# tomo.net
KiCad netlist of a schematic drawn in EAGLE
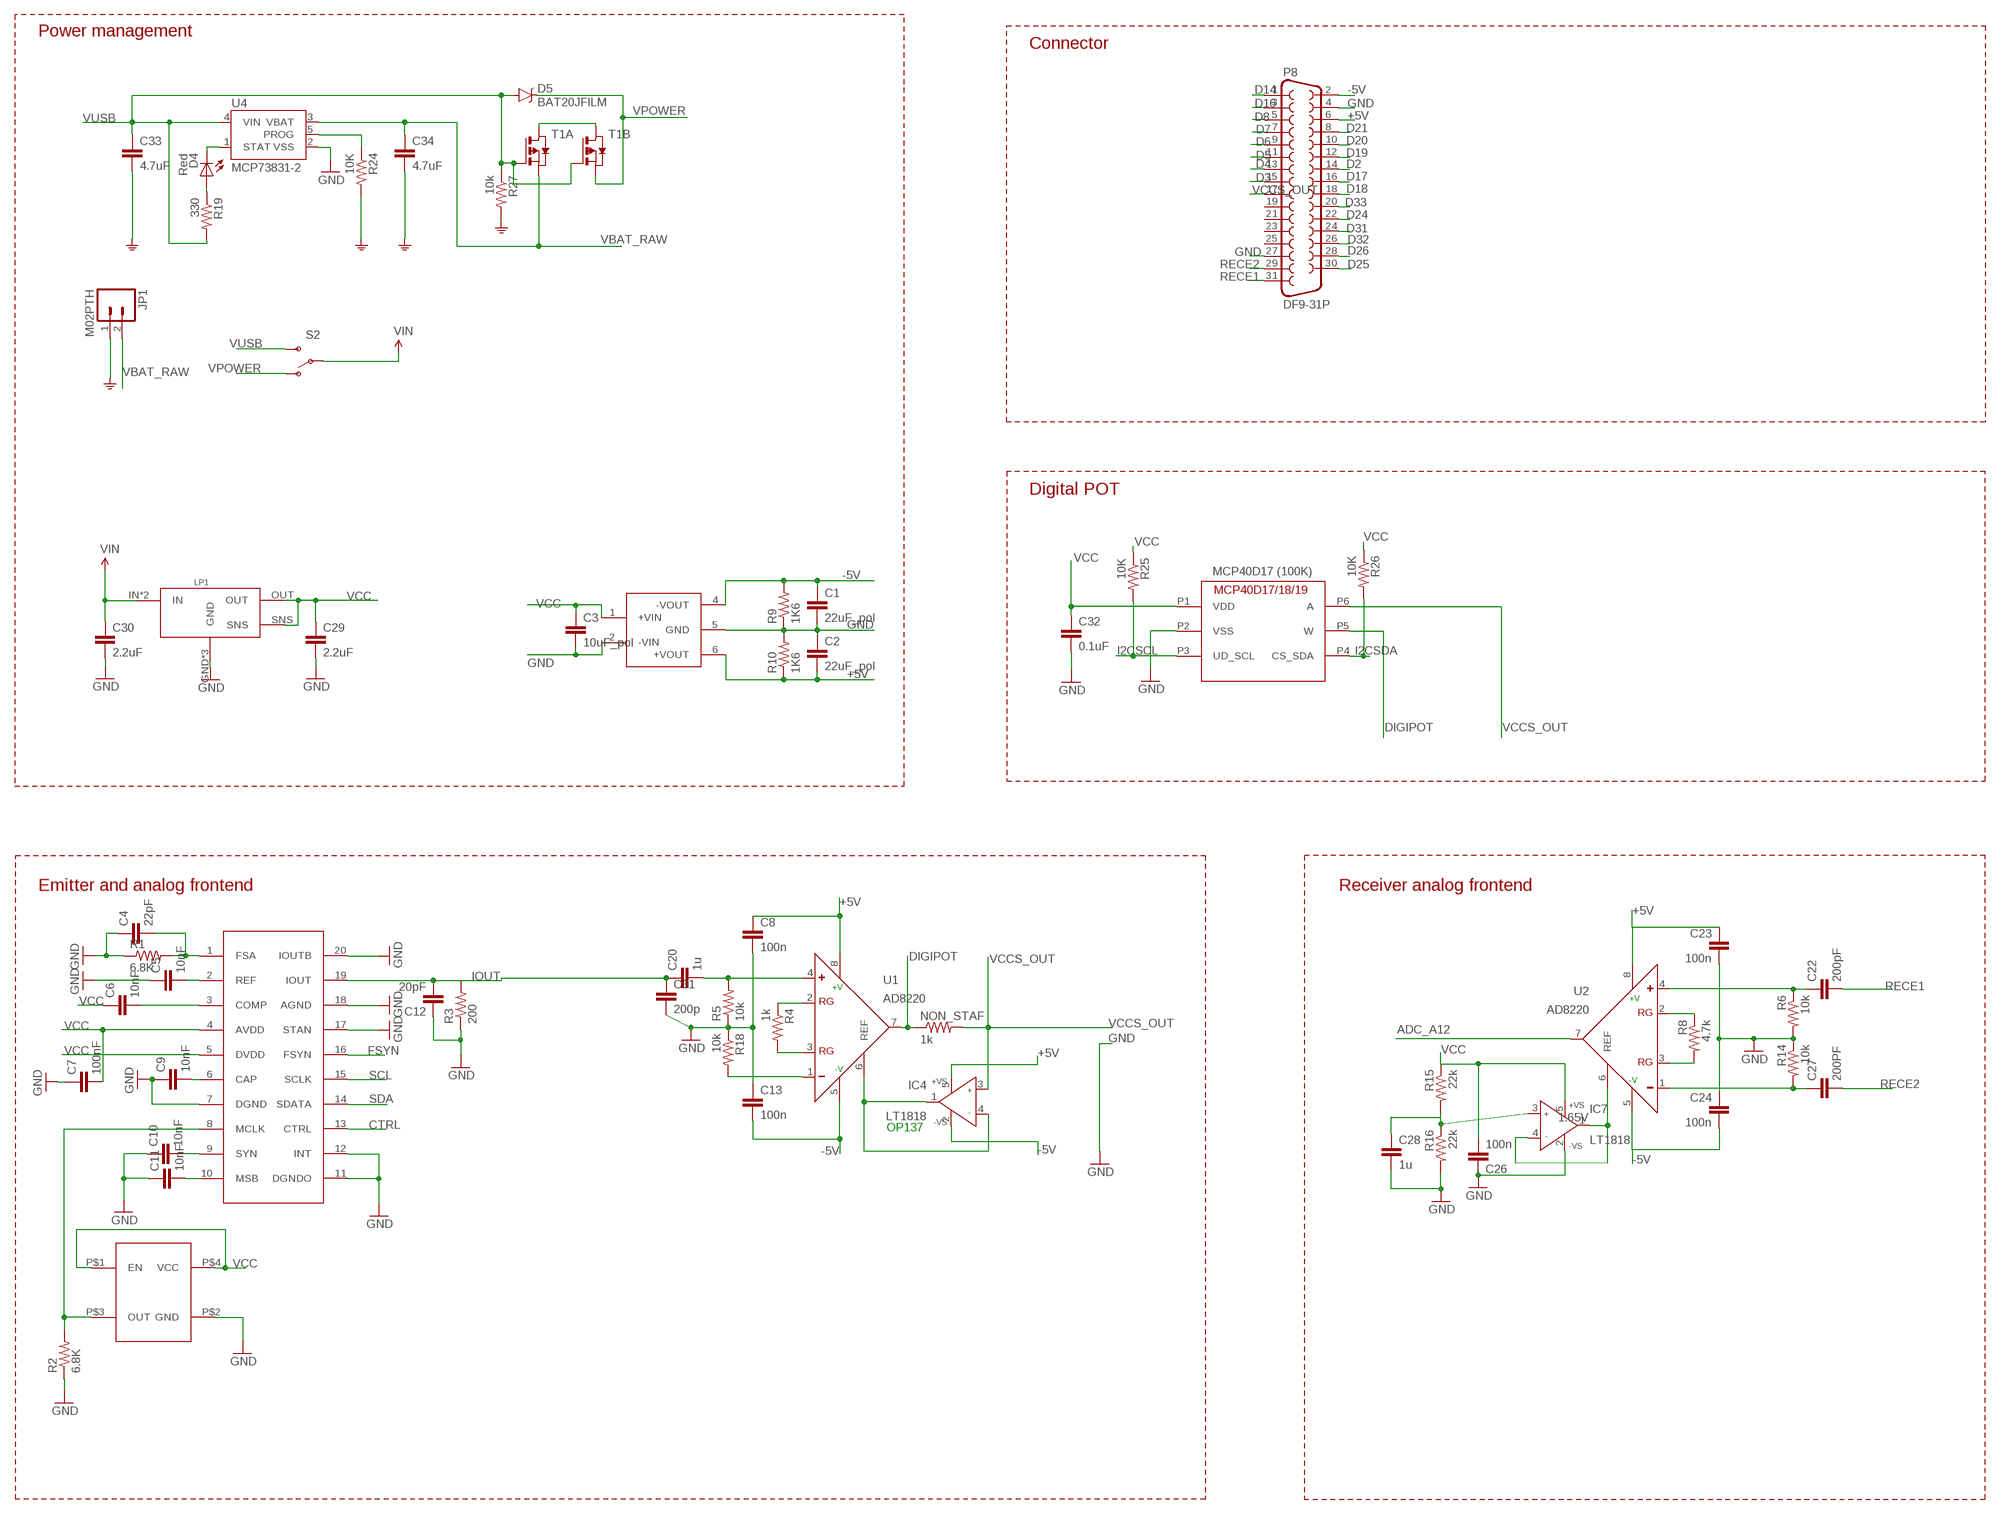
[diagram p0: schematic, sheet 1]
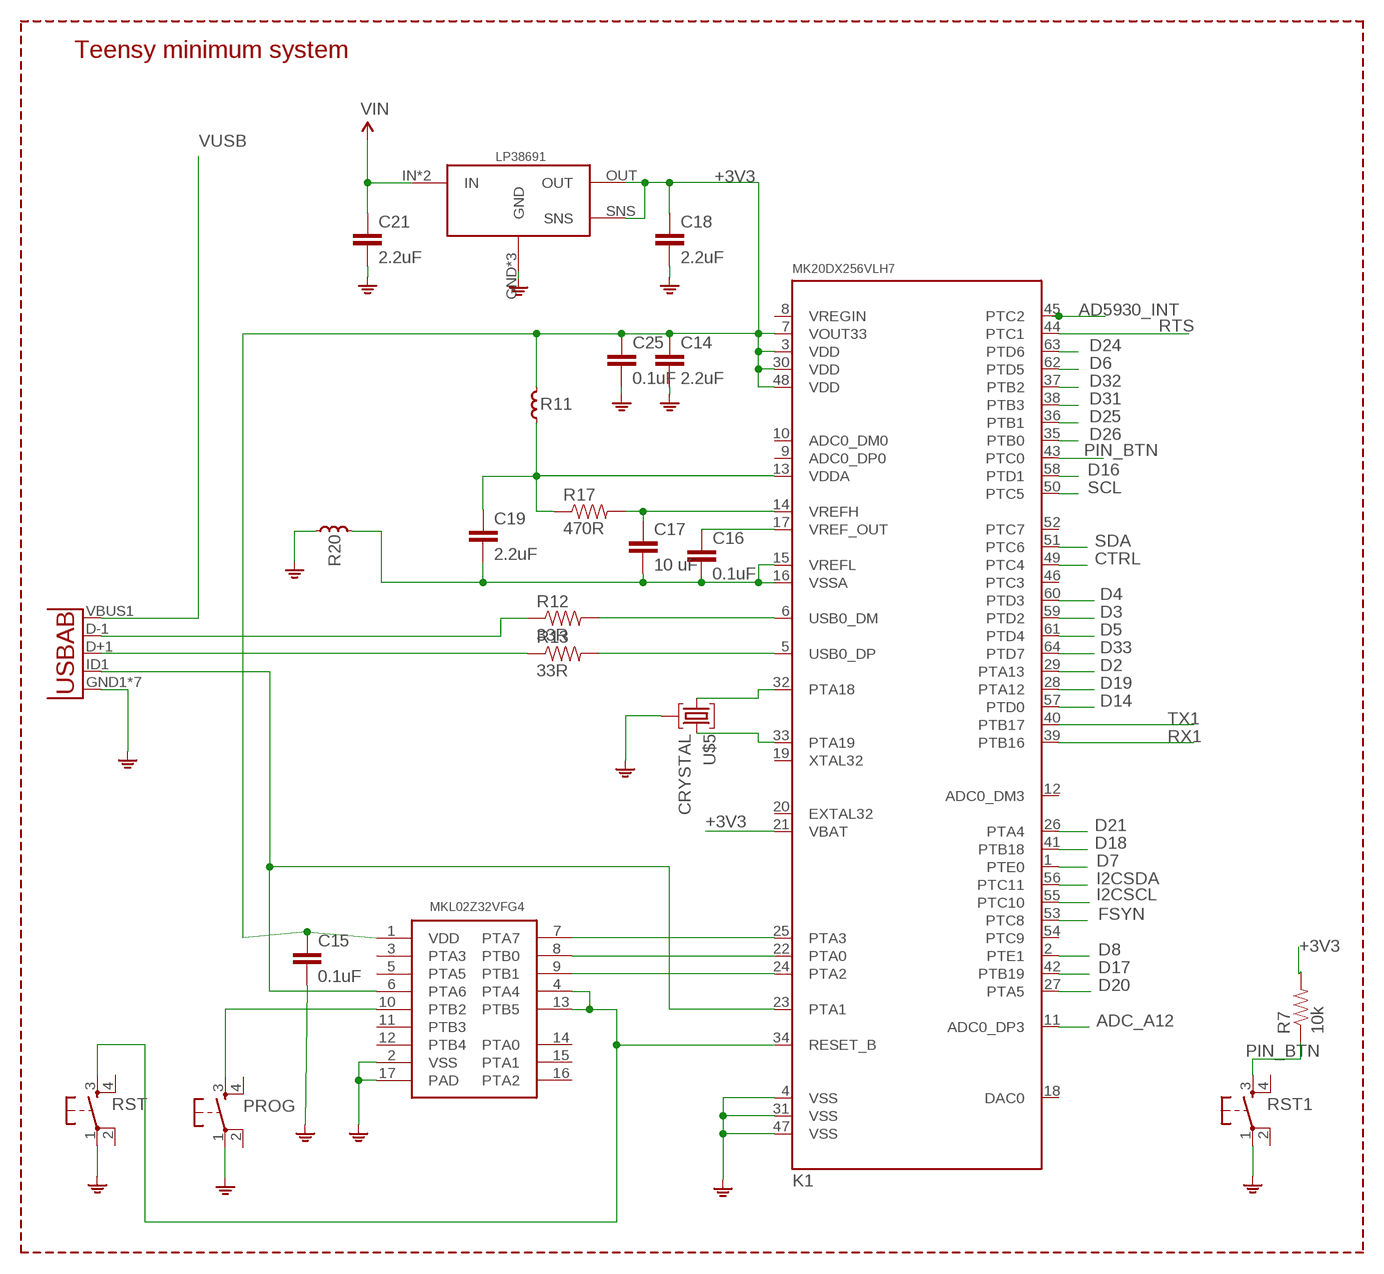
[diagram p1: schematic, sheet 2]
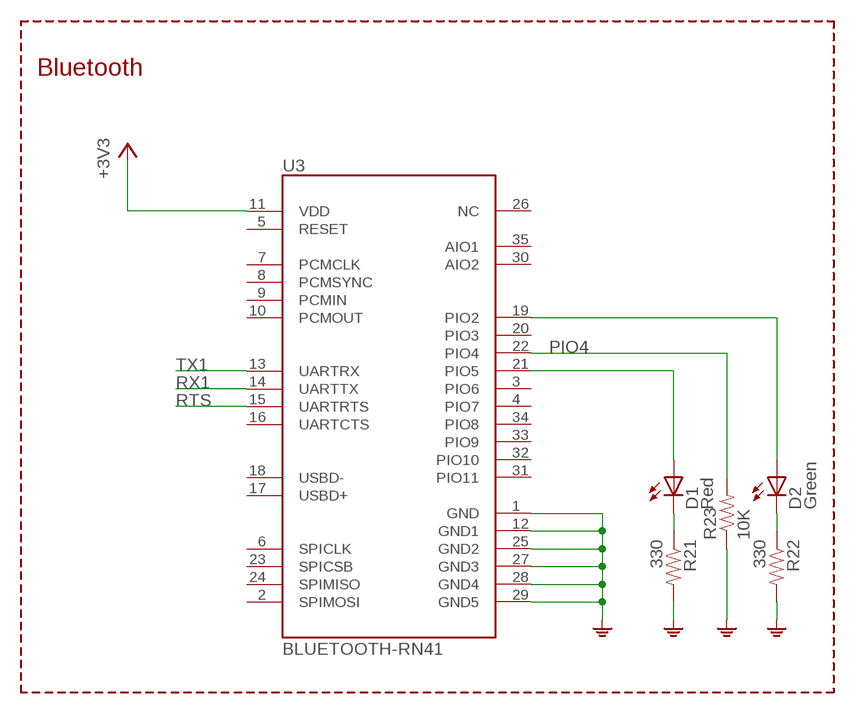
[diagram p2: schematic, sheet 3]

(export (version "E")
  (design (tool "Eeschema 10.0.6"))
  (components
    (comp (ref "C1")
      (value "22uF_pol")
      (footprint "eagle-import:0603-CAP")
      (libsource (lib "eagle-import") (part "0.1UF-25V(+80/-20%)(0603)"))
    )
    (comp (ref "C2")
      (value "22uF_pol")
      (footprint "eagle-import:0603-CAP")
      (libsource (lib "eagle-import") (part "0.1UF-25V(+80/-20%)(0603)"))
    )
    (comp (ref "C3")
      (value "10uF_pol")
      (footprint "eagle-import:0603-CAP")
      (libsource (lib "eagle-import") (part "0.1UF-25V(+80/-20%)(0603)"))
    )
    (comp (ref "C4")
      (value "22pF")
      (footprint "eagle-import:0603-CAP")
      (libsource (lib "eagle-import") (part "1.0UF-16V-10%(0603)"))
    )
    (comp (ref "C5")
      (value "10nF")
      (footprint "eagle-import:0603-CAP")
      (libsource (lib "eagle-import") (part "1.0UF-16V-10%(0603)"))
    )
    (comp (ref "C6")
      (value "10nF")
      (footprint "eagle-import:0603-CAP")
      (libsource (lib "eagle-import") (part "1.0UF-16V-10%(0603)"))
    )
    (comp (ref "C7")
      (value "100nF")
      (footprint "eagle-import:0603-CAP")
      (libsource (lib "eagle-import") (part "1.0UF-16V-10%(0603)"))
    )
    (comp (ref "C8")
      (value "100n")
      (footprint "eagle-import:0603-CAP")
      (libsource (lib "eagle-import") (part "0.1UF-25V(+80/-20%)(0603)"))
    )
    (comp (ref "C9")
      (value "10nF")
      (footprint "eagle-import:0603-CAP")
      (libsource (lib "eagle-import") (part "1.0UF-16V-10%(0603)"))
    )
    (comp (ref "C10")
      (value "10nF")
      (footprint "eagle-import:0603-CAP")
      (libsource (lib "eagle-import") (part "1.0UF-16V-10%(0603)"))
    )
    (comp (ref "C11")
      (value "10nF")
      (footprint "eagle-import:0603-CAP")
      (libsource (lib "eagle-import") (part "1.0UF-16V-10%(0603)"))
    )
    (comp (ref "C12")
      (value "20pF")
      (footprint "eagle-import:0603-CAP")
      (libsource (lib "eagle-import") (part "1.0UF-16V-10%(0603)"))
    )
    (comp (ref "C13")
      (value "100n")
      (footprint "eagle-import:0603-CAP")
      (libsource (lib "eagle-import") (part "0.1UF-25V(+80/-20%)(0603)"))
    )
    (comp (ref "C20")
      (value "1u")
      (footprint "eagle-import:0603-CAP")
      (libsource (lib "eagle-import") (part "0.1UF-25V(+80/-20%)(0603)"))
    )
    (comp (ref "C22")
      (value "200pF")
      (footprint "eagle-import:0603-CAP")
      (libsource (lib "eagle-import") (part "0.1UF-25V(+80/-20%)(0603)"))
    )
    (comp (ref "C23")
      (value "100n")
      (footprint "eagle-import:0603-CAP")
      (libsource (lib "eagle-import") (part "0.1UF-25V(+80/-20%)(0603)"))
    )
    (comp (ref "C24")
      (value "100n")
      (footprint "eagle-import:0603-CAP")
      (libsource (lib "eagle-import") (part "0.1UF-25V(+80/-20%)(0603)"))
    )
    (comp (ref "C26")
      (value "100n")
      (footprint "eagle-import:0603-CAP")
      (libsource (lib "eagle-import") (part "0.1UF-25V(+80/-20%)(0603)"))
    )
    (comp (ref "C27")
      (value "200PF")
      (footprint "eagle-import:0603-CAP")
      (libsource (lib "eagle-import") (part "0.1UF-25V(+80/-20%)(0603)"))
    )
    (comp (ref "C28")
      (value "1u")
      (footprint "eagle-import:0603-CAP")
      (libsource (lib "eagle-import") (part "0.1UF-25V(+80/-20%)(0603)"))
    )
    (comp (ref "C29")
      (value "2.2uF")
      (footprint "eagle-import:0402-CAP")
      (libsource (lib "eagle-import") (part "0.1UF-16V(+-10%)(0402)"))
    )
    (comp (ref "C30")
      (value "2.2uF")
      (footprint "eagle-import:0402-CAP")
      (libsource (lib "eagle-import") (part "0.1UF-16V(+-10%)(0402)"))
    )
    (comp (ref "C31")
      (value "200p")
      (footprint "eagle-import:0603-CAP")
      (libsource (lib "eagle-import") (part "0.1UF-25V(+80/-20%)(0603)"))
    )
    (comp (ref "C32")
      (value "0.1uF")
      (footprint "eagle-import:0402-CAP")
      (libsource (lib "eagle-import") (part "0.1UF-16V(+-10%)(0402)"))
    )
    (comp (ref "C33")
      (value "4.7uF")
      (footprint "eagle-import:0402-CAP")
      (libsource (lib "eagle-import") (part "CAP0402-CAP"))
    )
    (comp (ref "C34")
      (value "4.7uF")
      (footprint "eagle-import:0402-CAP")
      (libsource (lib "eagle-import") (part "CAP0402-CAP"))
    )
    (comp (ref "D4")
      (value "Red")
      (footprint "eagle-import:LED-0603")
      (libsource (lib "eagle-import") (part "LED0603"))
    )
    (comp (ref "D5")
      (value "BAT20JFILM")
      (footprint "eagle-import:SOD-323")
      (libsource (lib "eagle-import") (part "BAT20JFILM"))
    )
    (comp (ref "IC4")
      (value "LT1818")
      (footprint "eagle-import:SOT23-5")
      (fields (field (name "MF") "ALTERA CORPORATION") (field (name "MPN") "AD8541ARTZ-REEL7"))
      (libsource (lib "eagle-import") (part "AD8541RJ"))
    )
    (comp (ref "IC7")
      (value "LT1818")
      (footprint "eagle-import:SOT23-5")
      (fields (field (name "MF") "ALTERA CORPORATION") (field (name "MPN") "AD8541ARTZ-REEL7"))
      (libsource (lib "eagle-import") (part "AD8541RJ"))
    )
    (comp (ref "JP1")
      (value "M02PTH")
      (footprint "eagle-import:1X02")
      (libsource (lib "eagle-import") (part "M02PTH"))
    )
    (comp (ref "LP1")
      (value "LP38691SD")
      (footprint "eagle-import:WSON_6")
      (libsource (lib "eagle-import") (part "LP38691SD"))
    )
    (comp (ref "NON_STAF")
      (value "1k")
      (footprint "eagle-import:0603-RES")
      (libsource (lib "eagle-import") (part "1.2MOHMS-1/10W-1%(0603)"))
    )
    (comp (ref "P8")
      (value "DF9-31P")
      (footprint "eagle-import:DF9-31P")
      (libsource (lib "eagle-import") (part "DF9-31P"))
    )
    (comp (ref "R1")
      (value "6.8K")
      (footprint "eagle-import:0603")
      (libsource (lib "eagle-import") (part "1.5KOHM-1/10W-1%(0603)"))
    )
    (comp (ref "R2")
      (value "6.8K")
      (footprint "eagle-import:0603")
      (libsource (lib "eagle-import") (part "1.5KOHM-1/10W-1%(0603)"))
    )
    (comp (ref "R3")
      (value "200")
      (footprint "eagle-import:0603")
      (libsource (lib "eagle-import") (part "1.5KOHM-1/10W-1%(0603)"))
    )
    (comp (ref "R4")
      (value "1k")
      (footprint "eagle-import:0603-RES")
      (libsource (lib "eagle-import") (part "1.2MOHMS-1/10W-1%(0603)"))
    )
    (comp (ref "R5")
      (value "10k")
      (footprint "eagle-import:0603-RES")
      (libsource (lib "eagle-import") (part "1.2MOHMS-1/10W-1%(0603)"))
    )
    (comp (ref "R6")
      (value "10k")
      (footprint "eagle-import:0603")
      (libsource (lib "eagle-import") (part "0.05OHM-1/5W-1%(0603)"))
    )
    (comp (ref "R8")
      (value "4.7k")
      (footprint "eagle-import:0603")
      (libsource (lib "eagle-import") (part "0.05OHM-1/5W-1%(0603)"))
    )
    (comp (ref "R9")
      (value "1K6")
      (footprint "eagle-import:0603-RES")
      (libsource (lib "eagle-import") (part "2.2KOHM-1/10W-1%(0603)"))
    )
    (comp (ref "R10")
      (value "1K6")
      (footprint "eagle-import:0603-RES")
      (libsource (lib "eagle-import") (part "2.2KOHM-1/10W-1%(0603)"))
    )
    (comp (ref "R14")
      (value "10k")
      (footprint "eagle-import:0603")
      (libsource (lib "eagle-import") (part "0.05OHM-1/5W-1%(0603)"))
    )
    (comp (ref "R15")
      (value "22k")
      (footprint "eagle-import:0603")
      (libsource (lib "eagle-import") (part "0.05OHM-1/5W-1%(0603)"))
    )
    (comp (ref "R16")
      (value "22k")
      (footprint "eagle-import:0603")
      (libsource (lib "eagle-import") (part "0.05OHM-1/5W-1%(0603)"))
    )
    (comp (ref "R18")
      (value "10k")
      (footprint "eagle-import:0603-RES")
      (libsource (lib "eagle-import") (part "1.2MOHMS-1/10W-1%(0603)"))
    )
    (comp (ref "R19")
      (value "330")
      (footprint "eagle-import:0402-RES")
      (libsource (lib "eagle-import") (part "RESISTOR0402-RES"))
    )
    (comp (ref "R24")
      (value "10K")
      (footprint "eagle-import:0402-RES")
      (libsource (lib "eagle-import") (part "RESISTOR0402-RES"))
    )
    (comp (ref "R25")
      (value "10K")
      (footprint "eagle-import:0402-RES")
      (libsource (lib "eagle-import") (part "RESISTOR0402"))
    )
    (comp (ref "R26")
      (value "10K")
      (footprint "eagle-import:0402-RES")
      (libsource (lib "eagle-import") (part "RESISTOR0402"))
    )
    (comp (ref "R27")
      (value "10k")
      (footprint "eagle-import:0402-RES")
      (libsource (lib "eagle-import") (part "RESISTOR0402-RES"))
    )
    (comp (ref "S2")
      (value "SWITCH-SPDT-SMD-A")
      (footprint "eagle-import:SWITCH-SPST-SMD-A")
      (libsource (lib "eagle-import") (part "SWITCH-SPDT-SMD-A"))
    )
    (comp (ref "T1")
      (value "BSS84DW")
      (footprint "eagle-import:SOT363")
      (libsource (lib "eagle-import") (part "PMOSFET2"))
    )
    (comp (ref "U$2")
      (value "AD5930")
      (footprint "eagle-import:TSSOP-20")
      (libsource (lib "eagle-import") (part "AD5930"))
    )
    (comp (ref "U$3")
      (value "OSC")
      (footprint "eagle-import:OSC")
      (libsource (lib "eagle-import") (part "OSC"))
    )
    (comp (ref "U$4")
      (value "DCDC_CONVERTOR")
      (footprint "eagle-import:DCDC_CONVERTOR")
      (libsource (lib "eagle-import") (part "DCDC_CONVERTOR"))
    )
    (comp (ref "U$6")
      (value "MCP40D17/18/19")
      (footprint "eagle-import:SC70-6")
      (libsource (lib "eagle-import") (part "MCP40D17/18/19"))
    )
    (comp (ref "U1")
      (value "AD8220")
      (footprint "eagle-import:MSOP8")
      (libsource (lib "eagle-import") (part "AD8220"))
    )
    (comp (ref "U2")
      (value "AD8220")
      (footprint "eagle-import:MSOP8")
      (libsource (lib "eagle-import") (part "AD8220"))
    )
    (comp (ref "U4")
      (value "MCP73831-2")
      (footprint "eagle-import:SOT23-5")
      (libsource (lib "eagle-import") (part "MCP73831"))
    )
    (comp (ref "C14")
      (value "2.2uF")
      (footprint "eagle-import:0603-CAP")
      (libsource (lib "eagle-import") (part "0.1UF-25V(+80/-20%)(0603)"))
    )
    (comp (ref "C15")
      (value "0.1uF")
      (footprint "eagle-import:0402-CAP")
      (libsource (lib "eagle-import") (part "0.1UF-16V(+-10%)(0402)"))
    )
    (comp (ref "C16")
      (value "0.1uF")
      (footprint "eagle-import:0402-CAP")
      (libsource (lib "eagle-import") (part "0.1UF-16V(+-10%)(0402)"))
    )
    (comp (ref "C17")
      (value "10 uF")
      (footprint "eagle-import:0402-CAP")
      (libsource (lib "eagle-import") (part "0.1UF-16V(+-10%)(0402)"))
    )
    (comp (ref "C18")
      (value "2.2uF")
      (footprint "eagle-import:0402-CAP")
      (libsource (lib "eagle-import") (part "0.1UF-16V(+-10%)(0402)"))
    )
    (comp (ref "C19")
      (value "2.2uF")
      (footprint "eagle-import:0402-CAP")
      (libsource (lib "eagle-import") (part "0.1UF-16V(+-10%)(0402)"))
    )
    (comp (ref "C21")
      (value "2.2uF")
      (footprint "eagle-import:0402-CAP")
      (libsource (lib "eagle-import") (part "0.1UF-16V(+-10%)(0402)"))
    )
    (comp (ref "C25")
      (value "0.1uF")
      (footprint "eagle-import:0402-CAP")
      (libsource (lib "eagle-import") (part "0.1UF-16V(+-10%)(0402)"))
    )
    (comp (ref "K1")
      (value "MK20DX256VLH7")
      (footprint "eagle-import:LQFP64-05")
      (fields (field (name "MF") "NXP"))
      (libsource (lib "eagle-import") (part "MK20DX256VLH7"))
    )
    (comp (ref "LP38691")
      (value "LP38691SD")
      (footprint "eagle-import:WSON_6")
      (libsource (lib "eagle-import") (part "LP38691SD"))
    )
    (comp (ref "PROG")
      (value "KMR211GLFS")
      (footprint "eagle-import:TACTILE_SWITCH_SMD")
      (libsource (lib "eagle-import") (part "TAC_SWITCHSMD"))
    )
    (comp (ref "R7")
      (value "10k")
      (footprint "eagle-import:0402-RES")
      (libsource (lib "eagle-import") (part "22OHM1/10W1%(0402)"))
    )
    (comp (ref "R11")
      (value "FERRITE")
      (footprint "eagle-import:L0603")
      (fields (field (name "MF") "Murata Electronics") (field (name "MPN") " BLM18AG601SN1D"))
      (libsource (lib "eagle-import") (part "FERRITE"))
    )
    (comp (ref "R12")
      (value "33R")
      (footprint "eagle-import:0402-RES")
      (libsource (lib "eagle-import") (part "22OHM1/10W1%(0402)"))
    )
    (comp (ref "R13")
      (value "33R")
      (footprint "eagle-import:0402-RES")
      (libsource (lib "eagle-import") (part "22OHM1/10W1%(0402)"))
    )
    (comp (ref "R17")
      (value "470R")
      (footprint "eagle-import:0402-RES")
      (libsource (lib "eagle-import") (part "22OHM1/10W1%(0402)"))
    )
    (comp (ref "R20")
      (value "FERRITE")
      (footprint "eagle-import:L0603")
      (fields (field (name "MF") "Murata Electronics") (field (name "MPN") " BLM18AG601SN1D"))
      (libsource (lib "eagle-import") (part "FERRITE"))
    )
    (comp (ref "RST")
      (value "KMR211GLFS")
      (footprint "eagle-import:TACTILE_SWITCH_SMD")
      (libsource (lib "eagle-import") (part "TAC_SWITCHSMD"))
    )
    (comp (ref "RST1")
      (value "KMR211GLFS")
      (footprint "eagle-import:TACTILE_SWITCH_SMD")
      (libsource (lib "eagle-import") (part "TAC_SWITCHSMD"))
    )
    (comp (ref "U$5")
      (value "CRYSTAL")
      (footprint "eagle-import:CRYSTAL")
      (libsource (lib "eagle-import") (part "CRYSTAL"))
    )
    (comp (ref "U$14")
      (value "MKL02Z32VFG4_")
      (footprint "eagle-import:QFN16_3X3")
      (libsource (lib "eagle-import") (part "MKL02Z32VFG4_"))
    )
    (comp (ref "U5")
      (value "USB\"\"")
      (footprint "eagle-import:USB-MICRO-SMD")
      (libsource (lib "eagle-import") (part "USB{dblquote}{dblquote}"))
    )
    (comp (ref "D1")
      (value "Red")
      (footprint "eagle-import:LED-0603")
      (libsource (lib "eagle-import") (part "LED0603"))
    )
    (comp (ref "D2")
      (value "Green")
      (footprint "eagle-import:LED-0603")
      (libsource (lib "eagle-import") (part "LED0603"))
    )
    (comp (ref "R21")
      (value "330")
      (footprint "eagle-import:0402-RES")
      (libsource (lib "eagle-import") (part "RESISTOR0402-RES"))
    )
    (comp (ref "R22")
      (value "330")
      (footprint "eagle-import:0402-RES")
      (libsource (lib "eagle-import") (part "RESISTOR0402-RES"))
    )
    (comp (ref "R23")
      (value "10K")
      (footprint "eagle-import:0402-RES")
      (libsource (lib "eagle-import") (part "RESISTOR0402-RES"))
    )
    (comp (ref "U3")
      (value "BLUETOOTH-RN41")
      (footprint "eagle-import:RN41")
      (libsource (lib "eagle-import") (part "BLUETOOTH-RN41{dblquote}"))
    )
  )
  (nets
    (net (code "1") (name "+3V3") (class "Default")
      (node (ref "C14") (pin "1") (pinfunction "1_1") (pintype "passive"))
      (node (ref "C15") (pin "1") (pinfunction "1_1") (pintype "passive"))
      (node (ref "C18") (pin "1") (pinfunction "1_1") (pintype "passive"))
      (node (ref "C25") (pin "1") (pinfunction "1_1") (pintype "passive"))
      (node (ref "K1") (pin "21") (pinfunction "VBAT_21") (pintype "bidirectional"))
      (node (ref "K1") (pin "3") (pinfunction "VDD_3") (pintype "bidirectional"))
      (node (ref "K1") (pin "30") (pinfunction "VDD_30") (pintype "bidirectional"))
      (node (ref "K1") (pin "48") (pinfunction "VDD_48") (pintype "bidirectional"))
      (node (ref "K1") (pin "7") (pinfunction "VOUT33_7") (pintype "bidirectional"))
      (node (ref "LP38691") (pin "OUT") (pinfunction "OUT_OUT") (pintype "bidirectional"))
      (node (ref "LP38691") (pin "SNS") (pinfunction "SNS_SNS") (pintype "bidirectional"))
      (node (ref "R11") (pin "2") (pinfunction "2_2") (pintype "passive"))
      (node (ref "R7") (pin "2") (pinfunction "2_2") (pintype "passive"))
      (node (ref "U$14") (pin "1") (pinfunction "VDD_1") (pintype "bidirectional"))
      (node (ref "U3") (pin "11") (pinfunction "VDD_11") (pintype "bidirectional"))
    )
    (net (code "2") (name "+5V") (class "Default")
      (node (ref "C2") (pin "2") (pinfunction "2_2") (pintype "passive"))
      (node (ref "C23") (pin "1") (pinfunction "1_1") (pintype "passive"))
      (node (ref "C8") (pin "1") (pinfunction "1_1") (pintype "passive"))
      (node (ref "IC4") (pin "5") (pinfunction "+VS_5") (pintype "input"))
      (node (ref "P8") (pin "6") (pinfunction "6_6") (pintype "passive"))
      (node (ref "R10") (pin "1") (pinfunction "1_1") (pintype "passive"))
      (node (ref "U$4") (pin "6") (pinfunction "+VOUT_6") (pintype "bidirectional"))
      (node (ref "U1") (pin "8") (pinfunction "+V_8") (pintype "power_in"))
      (node (ref "U2") (pin "8") (pinfunction "+V_8") (pintype "power_in"))
    )
    (net (code "3") (name "-5V") (class "Default")
      (node (ref "C1") (pin "1") (pinfunction "1_1") (pintype "passive"))
      (node (ref "C13") (pin "2") (pinfunction "2_2") (pintype "passive"))
      (node (ref "C24") (pin "2") (pinfunction "2_2") (pintype "passive"))
      (node (ref "IC4") (pin "2") (pinfunction "-VS_2") (pintype "input"))
      (node (ref "P8") (pin "2") (pinfunction "2_2") (pintype "passive"))
      (node (ref "R9") (pin "2") (pinfunction "2_2") (pintype "passive"))
      (node (ref "U$4") (pin "4") (pinfunction "-VOUT_4") (pintype "bidirectional"))
      (node (ref "U1") (pin "5") (pinfunction "-V_5") (pintype "power_in"))
      (node (ref "U2") (pin "5") (pinfunction "-V_5") (pintype "power_in"))
    )
    (net (code "4") (name "1.65V") (class "Default")
      (node (ref "IC7") (pin "1") (pinfunction "OUT_1") (pintype "output"))
      (node (ref "IC7") (pin "4") (pinfunction "IN-_4") (pintype "input"))
      (node (ref "U2") (pin "6") (pinfunction "REF_6") (pintype "passive"))
    )
    (net (code "5") (name "AD5930_INT") (class "Default")
      (node (ref "K1") (pin "45") (pinfunction "PTC2_45") (pintype "bidirectional"))
    )
    (net (code "6") (name "ADC_A12") (class "Default")
      (node (ref "K1") (pin "11") (pinfunction "ADC0_DP3_11") (pintype "bidirectional"))
      (node (ref "U2") (pin "7") (pinfunction "OUT_7") (pintype "output"))
    )
    (net (code "7") (name "CTRL") (class "Default")
      (node (ref "K1") (pin "49") (pinfunction "PTC4_49") (pintype "bidirectional"))
      (node (ref "U$2") (pin "13") (pinfunction "CTRL_13") (pintype "bidirectional"))
    )
    (net (code "8") (name "D2") (class "Default")
      (node (ref "K1") (pin "29") (pinfunction "PTA13_29") (pintype "bidirectional"))
      (node (ref "P8") (pin "14") (pinfunction "14_14") (pintype "passive"))
    )
    (net (code "9") (name "D3") (class "Default")
      (node (ref "K1") (pin "59") (pinfunction "PTD2_59") (pintype "bidirectional"))
      (node (ref "P8") (pin "15") (pinfunction "15_15") (pintype "passive"))
    )
    (net (code "10") (name "D4") (class "Default")
      (node (ref "K1") (pin "60") (pinfunction "PTD3_60") (pintype "bidirectional"))
      (node (ref "P8") (pin "13") (pinfunction "13_13") (pintype "passive"))
    )
    (net (code "11") (name "D5") (class "Default")
      (node (ref "K1") (pin "61") (pinfunction "PTD4_61") (pintype "bidirectional"))
      (node (ref "P8") (pin "11") (pinfunction "11_11") (pintype "passive"))
    )
    (net (code "12") (name "D6") (class "Default")
      (node (ref "K1") (pin "62") (pinfunction "PTD5_62") (pintype "bidirectional"))
      (node (ref "P8") (pin "9") (pinfunction "9_9") (pintype "passive"))
    )
    (net (code "13") (name "D7") (class "Default")
      (node (ref "K1") (pin "1") (pinfunction "PTE0_1") (pintype "bidirectional"))
      (node (ref "P8") (pin "7") (pinfunction "7_7") (pintype "passive"))
    )
    (net (code "14") (name "D8") (class "Default")
      (node (ref "K1") (pin "2") (pinfunction "PTE1_2") (pintype "bidirectional"))
      (node (ref "P8") (pin "5") (pinfunction "5_5") (pintype "passive"))
    )
    (net (code "15") (name "D14") (class "Default")
      (node (ref "K1") (pin "57") (pinfunction "PTD0_57") (pintype "bidirectional"))
      (node (ref "P8") (pin "1") (pinfunction "1_1") (pintype "passive"))
    )
    (net (code "16") (name "D16") (class "Default")
      (node (ref "K1") (pin "58") (pinfunction "PTD1_58") (pintype "bidirectional"))
      (node (ref "P8") (pin "3") (pinfunction "3_3") (pintype "passive"))
    )
    (net (code "17") (name "D17") (class "Default")
      (node (ref "K1") (pin "42") (pinfunction "PTB19_42") (pintype "bidirectional"))
      (node (ref "P8") (pin "16") (pinfunction "16_16") (pintype "passive"))
    )
    (net (code "18") (name "D18") (class "Default")
      (node (ref "K1") (pin "41") (pinfunction "PTB18_41") (pintype "bidirectional"))
      (node (ref "P8") (pin "18") (pinfunction "18_18") (pintype "passive"))
    )
    (net (code "19") (name "D19") (class "Default")
      (node (ref "K1") (pin "28") (pinfunction "PTA12_28") (pintype "bidirectional"))
      (node (ref "P8") (pin "12") (pinfunction "12_12") (pintype "passive"))
    )
    (net (code "20") (name "D20") (class "Default")
      (node (ref "K1") (pin "27") (pinfunction "PTA5_27") (pintype "bidirectional"))
      (node (ref "P8") (pin "10") (pinfunction "10_10") (pintype "passive"))
    )
    (net (code "21") (name "D21") (class "Default")
      (node (ref "K1") (pin "26") (pinfunction "PTA4_26") (pintype "bidirectional"))
      (node (ref "P8") (pin "8") (pinfunction "8_8") (pintype "passive"))
    )
    (net (code "22") (name "D24") (class "Default")
      (node (ref "K1") (pin "63") (pinfunction "PTD6_63") (pintype "bidirectional"))
      (node (ref "P8") (pin "22") (pinfunction "22_22") (pintype "passive"))
    )
    (net (code "23") (name "D25") (class "Default")
      (node (ref "K1") (pin "36") (pinfunction "PTB1_36") (pintype "bidirectional"))
      (node (ref "P8") (pin "30") (pinfunction "30_30") (pintype "passive"))
    )
    (net (code "24") (name "D26") (class "Default")
      (node (ref "K1") (pin "35") (pinfunction "PTB0_35") (pintype "bidirectional"))
      (node (ref "P8") (pin "28") (pinfunction "28_28") (pintype "passive"))
    )
    (net (code "25") (name "D31") (class "Default")
      (node (ref "K1") (pin "38") (pinfunction "PTB3_38") (pintype "bidirectional"))
      (node (ref "P8") (pin "24") (pinfunction "24_24") (pintype "passive"))
    )
    (net (code "26") (name "D32") (class "Default")
      (node (ref "K1") (pin "37") (pinfunction "PTB2_37") (pintype "bidirectional"))
      (node (ref "P8") (pin "26") (pinfunction "26_26") (pintype "passive"))
    )
    (net (code "27") (name "D33") (class "Default")
      (node (ref "K1") (pin "64") (pinfunction "PTD7_64") (pintype "bidirectional"))
      (node (ref "P8") (pin "20") (pinfunction "20_20") (pintype "passive"))
    )
    (net (code "28") (name "DIGIPOT") (class "Default")
      (node (ref "NON_STAF") (pin "1") (pinfunction "1_1") (pintype "passive"))
      (node (ref "U$6") (pin "P5") (pinfunction "W_P5") (pintype "bidirectional"))
      (node (ref "U1") (pin "7") (pinfunction "OUT_7") (pintype "output"))
    )
    (net (code "29") (name "FSYN") (class "Default")
      (node (ref "K1") (pin "53") (pinfunction "PTC8_53") (pintype "bidirectional"))
      (node (ref "U$2") (pin "16") (pinfunction "FSYN_16") (pintype "bidirectional"))
    )
    (net (code "30") (name "GND") (class "Default")
      (node (ref "C1") (pin "2") (pinfunction "2_2") (pintype "passive"))
      (node (ref "C10") (pin "1") (pinfunction "1_1") (pintype "passive"))
      (node (ref "C11") (pin "1") (pinfunction "1_1") (pintype "passive"))
      (node (ref "C12") (pin "1") (pinfunction "1_1") (pintype "passive"))
      (node (ref "C13") (pin "1") (pinfunction "1_1") (pintype "passive"))
      (node (ref "C14") (pin "2") (pinfunction "2_2") (pintype "passive"))
      (node (ref "C15") (pin "2") (pinfunction "2_2") (pintype "passive"))
      (node (ref "C18") (pin "2") (pinfunction "2_2") (pintype "passive"))
      (node (ref "C2") (pin "1") (pinfunction "1_1") (pintype "passive"))
      (node (ref "C21") (pin "2") (pinfunction "2_2") (pintype "passive"))
      (node (ref "C23") (pin "2") (pinfunction "2_2") (pintype "passive"))
      (node (ref "C24") (pin "1") (pinfunction "1_1") (pintype "passive"))
      (node (ref "C25") (pin "2") (pinfunction "2_2") (pintype "passive"))
      (node (ref "C26") (pin "1") (pinfunction "1_1") (pintype "passive"))
      (node (ref "C28") (pin "2") (pinfunction "2_2") (pintype "passive"))
      (node (ref "C29") (pin "2") (pinfunction "2_2") (pintype "passive"))
      (node (ref "C3") (pin "2") (pinfunction "2_2") (pintype "passive"))
      (node (ref "C30") (pin "2") (pinfunction "2_2") (pintype "passive"))
      (node (ref "C31") (pin "2") (pinfunction "2_2") (pintype "passive"))
      (node (ref "C32") (pin "2") (pinfunction "2_2") (pintype "passive"))
      (node (ref "C33") (pin "2") (pinfunction "2_2") (pintype "passive"))
      (node (ref "C34") (pin "2") (pinfunction "2_2") (pintype "passive"))
      (node (ref "C4") (pin "1") (pinfunction "1_1") (pintype "passive"))
      (node (ref "C5") (pin "1") (pinfunction "1_1") (pintype "passive"))
      (node (ref "C7") (pin "1") (pinfunction "1_1") (pintype "passive"))
      (node (ref "C8") (pin "2") (pinfunction "2_2") (pintype "passive"))
      (node (ref "C9") (pin "1") (pinfunction "1_1") (pintype "passive"))
      (node (ref "IC7") (pin "2") (pinfunction "-VS_2") (pintype "input"))
      (node (ref "JP1") (pin "1") (pinfunction "1_1") (pintype "passive"))
      (node (ref "K1") (pin "31") (pinfunction "VSS_31") (pintype "bidirectional"))
      (node (ref "K1") (pin "4") (pinfunction "VSS_4") (pintype "bidirectional"))
      (node (ref "K1") (pin "47") (pinfunction "VSS_47") (pintype "bidirectional"))
      (node (ref "LP1") (pin "GND") (pinfunction "GND_GND") (pintype "bidirectional"))
      (node (ref "LP1") (pin "N/C") (pinfunction "GND_N/C") (pintype "bidirectional"))
      (node (ref "LP1") (pin "THERMAL") (pinfunction "GND_THERMAL") (pintype "bidirectional"))
      (node (ref "LP38691") (pin "GND") (pinfunction "GND_GND") (pintype "bidirectional"))
      (node (ref "LP38691") (pin "N/C") (pinfunction "GND_N/C") (pintype "bidirectional"))
      (node (ref "LP38691") (pin "THERMAL") (pinfunction "GND_THERMAL") (pintype "bidirectional"))
      (node (ref "P8") (pin "27") (pinfunction "27_27") (pintype "passive"))
      (node (ref "P8") (pin "4") (pinfunction "4_4") (pintype "passive"))
      (node (ref "PROG") (pin "1") (pinfunction "1_1") (pintype "passive"))
      (node (ref "R1") (pin "1") (pinfunction "1_1") (pintype "passive"))
      (node (ref "R10") (pin "2") (pinfunction "2_2") (pintype "passive"))
      (node (ref "R14") (pin "1") (pinfunction "1_1") (pintype "passive"))
      (node (ref "R16") (pin "2") (pinfunction "2_2") (pintype "passive"))
      (node (ref "R18") (pin "1") (pinfunction "1_1") (pintype "passive"))
      (node (ref "R2") (pin "1") (pinfunction "1_1") (pintype "passive"))
      (node (ref "R20") (pin "1") (pinfunction "1_1") (pintype "passive"))
      (node (ref "R21") (pin "2") (pinfunction "2_2") (pintype "passive"))
      (node (ref "R22") (pin "2") (pinfunction "2_2") (pintype "passive"))
      (node (ref "R23") (pin "1") (pinfunction "1_1") (pintype "passive"))
      (node (ref "R24") (pin "2") (pinfunction "2_2") (pintype "passive"))
      (node (ref "R27") (pin "2") (pinfunction "2_2") (pintype "passive"))
      (node (ref "R3") (pin "1") (pinfunction "1_1") (pintype "passive"))
      (node (ref "R5") (pin "1") (pinfunction "1_1") (pintype "passive"))
      (node (ref "R6") (pin "2") (pinfunction "2_2") (pintype "passive"))
      (node (ref "R9") (pin "1") (pinfunction "1_1") (pintype "passive"))
      (node (ref "RST") (pin "1") (pinfunction "1_1") (pintype "passive"))
      (node (ref "RST1") (pin "1") (pinfunction "1_1") (pintype "passive"))
      (node (ref "U$14") (pin "17") (pinfunction "PAD_17") (pintype "bidirectional"))
      (node (ref "U$14") (pin "2") (pinfunction "VSS_2") (pintype "bidirectional"))
      (node (ref "U$2") (pin "11") (pinfunction "DGNDO_11") (pintype "bidirectional"))
      (node (ref "U$2") (pin "12") (pinfunction "INT_12") (pintype "bidirectional"))
      (node (ref "U$2") (pin "17") (pinfunction "STAN_17") (pintype "bidirectional"))
      (node (ref "U$2") (pin "18") (pinfunction "AGND_18") (pintype "bidirectional"))
      (node (ref "U$2") (pin "20") (pinfunction "IOUTB_20") (pintype "bidirectional"))
      (node (ref "U$2") (pin "7") (pinfunction "DGND_7") (pintype "bidirectional"))
      (node (ref "U$3") (pin "P$2") (pinfunction "GND_P$2") (pintype "bidirectional"))
      (node (ref "U$4") (pin "2") (pinfunction "-VIN_2") (pintype "bidirectional"))
      (node (ref "U$4") (pin "5") (pinfunction "GND_5") (pintype "bidirectional"))
      (node (ref "U$5") (pin "GND1") (pinfunction "2_GND1") (pintype "passive"))
      (node (ref "U$5") (pin "GND2") (pinfunction "2_GND2") (pintype "passive"))
      (node (ref "U$6") (pin "P2") (pinfunction "VSS_P2") (pintype "power_in"))
      (node (ref "U3") (pin "1") (pinfunction "GND_1") (pintype "bidirectional"))
      (node (ref "U3") (pin "12") (pinfunction "GND1_12") (pintype "bidirectional"))
      (node (ref "U3") (pin "25") (pinfunction "GND2_25") (pintype "bidirectional"))
      (node (ref "U3") (pin "27") (pinfunction "GND3_27") (pintype "bidirectional"))
      (node (ref "U3") (pin "28") (pinfunction "GND4_28") (pintype "bidirectional"))
      (node (ref "U3") (pin "29") (pinfunction "GND5_29") (pintype "bidirectional"))
      (node (ref "U4") (pin "2") (pinfunction "VSS_2") (pintype "power_in"))
      (node (ref "U5") (pin "GND1") (pinfunction "GND_GND1") (pintype "bidirectional"))
      (node (ref "U5") (pin "P$1") (pinfunction "GND_P$1") (pintype "bidirectional"))
      (node (ref "U5") (pin "P$2") (pinfunction "GND_P$2") (pintype "bidirectional"))
      (node (ref "U5") (pin "P$3") (pinfunction "GND_P$3") (pintype "bidirectional"))
      (node (ref "U5") (pin "P$4") (pinfunction "GND_P$4") (pintype "bidirectional"))
      (node (ref "U5") (pin "P$5") (pinfunction "GND_P$5") (pintype "bidirectional"))
      (node (ref "U5") (pin "P$6") (pinfunction "GND_P$6") (pintype "bidirectional"))
    )
    (net (code "31") (name "I2CSCL") (class "Default")
      (node (ref "K1") (pin "55") (pinfunction "PTC10_55") (pintype "bidirectional"))
      (node (ref "R25") (pin "2") (pinfunction "2_2") (pintype "passive"))
      (node (ref "U$6") (pin "P3") (pinfunction "UD_SCL_P3") (pintype "bidirectional"))
    )
    (net (code "32") (name "I2CSDA") (class "Default")
      (node (ref "K1") (pin "56") (pinfunction "PTC11_56") (pintype "bidirectional"))
      (node (ref "R26") (pin "2") (pinfunction "2_2") (pintype "passive"))
      (node (ref "U$6") (pin "P4") (pinfunction "CS_SDA_P4") (pintype "bidirectional"))
    )
    (net (code "33") (name "IOUT") (class "Default")
      (node (ref "C12") (pin "2") (pinfunction "2_2") (pintype "passive"))
      (node (ref "C20") (pin "1") (pinfunction "1_1") (pintype "passive"))
      (node (ref "C31") (pin "1") (pinfunction "1_1") (pintype "passive"))
      (node (ref "R3") (pin "2") (pinfunction "2_2") (pintype "passive"))
      (node (ref "U$2") (pin "19") (pinfunction "IOUT_19") (pintype "bidirectional"))
    )
    (net (code "34") (name "Net-(D1-PadC)") (class "Default")
      (node (ref "D1") (pin "C") (pinfunction "C_C") (pintype "passive"))
      (node (ref "R21") (pin "1") (pinfunction "1_1") (pintype "passive"))
    )
    (net (code "35") (name "Net-(D2-PadC)") (class "Default")
      (node (ref "D2") (pin "C") (pinfunction "C_C") (pintype "passive"))
      (node (ref "R22") (pin "1") (pinfunction "1_1") (pintype "passive"))
    )
    (net (code "36") (name "Net-(D4-PadA)") (class "Default")
      (node (ref "D4") (pin "A") (pinfunction "A_A") (pintype "passive"))
      (node (ref "R19") (pin "1") (pinfunction "1_1") (pintype "passive"))
    )
    (net (code "37") (name "Net-(IC4-IN-)") (class "Default")
      (node (ref "IC4") (pin "1") (pinfunction "OUT_1") (pintype "output"))
      (node (ref "IC4") (pin "4") (pinfunction "IN-_4") (pintype "input"))
      (node (ref "U1") (pin "6") (pinfunction "REF_6") (pintype "passive"))
    )
    (net (code "38") (name "Net-(IC7-IN+)") (class "Default")
      (node (ref "C28") (pin "1") (pinfunction "1_1") (pintype "passive"))
      (node (ref "IC7") (pin "3") (pinfunction "IN+_3") (pintype "input"))
      (node (ref "R15") (pin "2") (pinfunction "2_2") (pintype "passive"))
      (node (ref "R16") (pin "1") (pinfunction "1_1") (pintype "passive"))
    )
    (net (code "39") (name "Net-(K1-PTA0)") (class "Default")
      (node (ref "K1") (pin "22") (pinfunction "PTA0_22") (pintype "bidirectional"))
      (node (ref "U$14") (pin "8") (pinfunction "PTB0_8") (pintype "bidirectional"))
    )
    (net (code "40") (name "Net-(K1-PTA1)") (class "Default")
      (node (ref "K1") (pin "23") (pinfunction "PTA1_23") (pintype "bidirectional"))
      (node (ref "U$14") (pin "6") (pinfunction "PTA6_6") (pintype "bidirectional"))
      (node (ref "U5") (pin "ID1") (pinfunction "USBID_ID1") (pintype "bidirectional"))
    )
    (net (code "41") (name "Net-(K1-PTA2)") (class "Default")
      (node (ref "K1") (pin "24") (pinfunction "PTA2_24") (pintype "bidirectional"))
      (node (ref "U$14") (pin "9") (pinfunction "PTB1_9") (pintype "bidirectional"))
    )
    (net (code "42") (name "Net-(K1-PTA3)") (class "Default")
      (node (ref "K1") (pin "25") (pinfunction "PTA3_25") (pintype "bidirectional"))
      (node (ref "U$14") (pin "7") (pinfunction "PTA7_7") (pintype "bidirectional"))
    )
    (net (code "43") (name "Net-(K1-PTA18)") (class "Default")
      (node (ref "K1") (pin "32") (pinfunction "PTA18_32") (pintype "bidirectional"))
      (node (ref "U$5") (pin "SIG1") (pinfunction "1_SIG1") (pintype "passive"))
    )
    (net (code "44") (name "Net-(K1-PTA19)") (class "Default")
      (node (ref "K1") (pin "33") (pinfunction "PTA19_33") (pintype "bidirectional"))
      (node (ref "U$5") (pin "SIG2") (pinfunction "3_SIG2") (pintype "passive"))
    )
    (net (code "45") (name "Net-(K1-RESET_B)") (class "Default")
      (node (ref "K1") (pin "34") (pinfunction "RESET_B_34") (pintype "bidirectional"))
      (node (ref "RST") (pin "3") (pinfunction "3_3") (pintype "passive"))
      (node (ref "U$14") (pin "13") (pinfunction "PTB5_13") (pintype "bidirectional"))
      (node (ref "U$14") (pin "4") (pinfunction "PTA4_4") (pintype "bidirectional"))
    )
    (net (code "46") (name "Net-(K1-USB0_DM)") (class "Default")
      (node (ref "K1") (pin "6") (pinfunction "USB0_DM_6") (pintype "bidirectional"))
      (node (ref "R12") (pin "2") (pinfunction "2_2") (pintype "passive"))
    )
    (net (code "47") (name "Net-(K1-USB0_DP)") (class "Default")
      (node (ref "K1") (pin "5") (pinfunction "USB0_DP_5") (pintype "bidirectional"))
      (node (ref "R13") (pin "2") (pinfunction "2_2") (pintype "passive"))
    )
    (net (code "48") (name "Net-(K1-VDDA)") (class "Default")
      (node (ref "C19") (pin "1") (pinfunction "1_1") (pintype "passive"))
      (node (ref "K1") (pin "13") (pinfunction "VDDA_13") (pintype "bidirectional"))
      (node (ref "R11") (pin "1") (pinfunction "1_1") (pintype "passive"))
      (node (ref "R17") (pin "1") (pinfunction "1_1") (pintype "passive"))
    )
    (net (code "49") (name "Net-(K1-VREFH)") (class "Default")
      (node (ref "C17") (pin "1") (pinfunction "1_1") (pintype "passive"))
      (node (ref "K1") (pin "14") (pinfunction "VREFH_14") (pintype "bidirectional"))
      (node (ref "R17") (pin "2") (pinfunction "2_2") (pintype "passive"))
    )
    (net (code "50") (name "Net-(K1-VREFL)") (class "Default")
      (node (ref "C16") (pin "2") (pinfunction "2_2") (pintype "passive"))
      (node (ref "C17") (pin "2") (pinfunction "2_2") (pintype "passive"))
      (node (ref "C19") (pin "2") (pinfunction "2_2") (pintype "passive"))
      (node (ref "K1") (pin "15") (pinfunction "VREFL_15") (pintype "bidirectional"))
      (node (ref "K1") (pin "16") (pinfunction "VSSA_16") (pintype "bidirectional"))
      (node (ref "R20") (pin "2") (pinfunction "2_2") (pintype "passive"))
    )
    (net (code "51") (name "Net-(K1-VREF_OUT)") (class "Default")
      (node (ref "C16") (pin "1") (pinfunction "1_1") (pintype "passive"))
      (node (ref "K1") (pin "17") (pinfunction "VREF_OUT_17") (pintype "bidirectional"))
    )
    (net (code "52") (name "Net-(R4-Pad1)") (class "Default")
      (node (ref "R4") (pin "1") (pinfunction "1_1") (pintype "passive"))
      (node (ref "U1") (pin "2") (pinfunction "RG_2") (pintype "passive"))
    )
    (net (code "53") (name "Net-(R4-Pad2)") (class "Default")
      (node (ref "R4") (pin "2") (pinfunction "2_2") (pintype "passive"))
      (node (ref "U1") (pin "3") (pinfunction "RG_3") (pintype "passive"))
    )
    (net (code "54") (name "Net-(R8-Pad1)") (class "Default")
      (node (ref "R8") (pin "1") (pinfunction "1_1") (pintype "passive"))
      (node (ref "U2") (pin "2") (pinfunction "RG_2") (pintype "passive"))
    )
    (net (code "55") (name "Net-(R8-Pad2)") (class "Default")
      (node (ref "R8") (pin "2") (pinfunction "2_2") (pintype "passive"))
      (node (ref "U2") (pin "3") (pinfunction "RG_3") (pintype "passive"))
    )
    (net (code "56") (name "Net-(T1A-D)") (class "Default")
      (node (ref "T1") (pin "3") (pinfunction "D_3") (pintype "passive"))
      (node (ref "T1") (pin "6") (pinfunction "D_6") (pintype "passive"))
    )
    (net (code "57") (name "Net-(U$2-CAP)") (class "Default")
      (node (ref "C9") (pin "2") (pinfunction "2_2") (pintype "passive"))
      (node (ref "U$2") (pin "6") (pinfunction "CAP_6") (pintype "bidirectional"))
    )
    (net (code "58") (name "Net-(U$2-COMP)") (class "Default")
      (node (ref "C6") (pin "2") (pinfunction "2_2") (pintype "passive"))
      (node (ref "U$2") (pin "3") (pinfunction "COMP_3") (pintype "bidirectional"))
    )
    (net (code "59") (name "Net-(U$2-FSA)") (class "Default")
      (node (ref "C4") (pin "2") (pinfunction "2_2") (pintype "passive"))
      (node (ref "R1") (pin "2") (pinfunction "2_2") (pintype "passive"))
      (node (ref "U$2") (pin "1") (pinfunction "FSA_1") (pintype "bidirectional"))
    )
    (net (code "60") (name "Net-(U$2-MCLK)") (class "Default")
      (node (ref "R2") (pin "2") (pinfunction "2_2") (pintype "passive"))
      (node (ref "U$2") (pin "8") (pinfunction "MCLK_8") (pintype "bidirectional"))
      (node (ref "U$3") (pin "P$3") (pinfunction "OUT_P$3") (pintype "bidirectional"))
    )
    (net (code "61") (name "Net-(U$2-MSB)") (class "Default")
      (node (ref "C11") (pin "2") (pinfunction "2_2") (pintype "passive"))
      (node (ref "U$2") (pin "10") (pinfunction "MSB_10") (pintype "bidirectional"))
    )
    (net (code "62") (name "Net-(U$2-REF)") (class "Default")
      (node (ref "C5") (pin "2") (pinfunction "2_2") (pintype "passive"))
      (node (ref "U$2") (pin "2") (pinfunction "REF_2") (pintype "bidirectional"))
    )
    (net (code "63") (name "Net-(U$2-SYN)") (class "Default")
      (node (ref "C10") (pin "2") (pinfunction "2_2") (pintype "passive"))
      (node (ref "U$2") (pin "9") (pinfunction "SYN_9") (pintype "bidirectional"))
    )
    (net (code "64") (name "Net-(U$14-PTB2)") (class "Default")
      (node (ref "PROG") (pin "3") (pinfunction "3_3") (pintype "passive"))
      (node (ref "U$14") (pin "10") (pinfunction "PTB2_10") (pintype "bidirectional"))
    )
    (net (code "65") (name "Net-(U1-+)") (class "Default")
      (node (ref "C20") (pin "2") (pinfunction "2_2") (pintype "passive"))
      (node (ref "R5") (pin "2") (pinfunction "2_2") (pintype "passive"))
      (node (ref "U1") (pin "4") (pinfunction "+_4") (pintype "input"))
    )
    (net (code "66") (name "Net-(U1--)") (class "Default")
      (node (ref "R18") (pin "2") (pinfunction "2_2") (pintype "passive"))
      (node (ref "U1") (pin "1") (pinfunction "-_1") (pintype "input"))
    )
    (net (code "67") (name "Net-(U2-+)") (class "Default")
      (node (ref "C22") (pin "1") (pinfunction "1_1") (pintype "passive"))
      (node (ref "R6") (pin "1") (pinfunction "1_1") (pintype "passive"))
      (node (ref "U2") (pin "4") (pinfunction "+_4") (pintype "input"))
    )
    (net (code "68") (name "Net-(U2--)") (class "Default")
      (node (ref "C27") (pin "1") (pinfunction "1_1") (pintype "passive"))
      (node (ref "R14") (pin "2") (pinfunction "2_2") (pintype "passive"))
      (node (ref "U2") (pin "1") (pinfunction "-_1") (pintype "input"))
    )
    (net (code "69") (name "Net-(U3-PIO2)") (class "Default")
      (node (ref "D2") (pin "A") (pinfunction "A_A") (pintype "passive"))
      (node (ref "U3") (pin "19") (pinfunction "PIO2_19") (pintype "bidirectional"))
    )
    (net (code "70") (name "Net-(U3-PIO5)") (class "Default")
      (node (ref "D1") (pin "A") (pinfunction "A_A") (pintype "passive"))
      (node (ref "U3") (pin "21") (pinfunction "PIO5_21") (pintype "bidirectional"))
    )
    (net (code "71") (name "Net-(U4-PROG)") (class "Default")
      (node (ref "R24") (pin "1") (pinfunction "1_1") (pintype "passive"))
      (node (ref "U4") (pin "5") (pinfunction "PROG_5") (pintype "input"))
    )
    (net (code "72") (name "Net-(U4-STAT)") (class "Default")
      (node (ref "D4") (pin "C") (pinfunction "C_C") (pintype "passive"))
      (node (ref "U4") (pin "1") (pinfunction "STAT_1") (pintype "output"))
    )
    (net (code "73") (name "Net-(U5-D+)") (class "Default")
      (node (ref "R13") (pin "1") (pinfunction "1_1") (pintype "passive"))
      (node (ref "U5") (pin "D+1") (pinfunction "D+_D+1") (pintype "bidirectional"))
    )
    (net (code "74") (name "Net-(U5-D-)") (class "Default")
      (node (ref "R12") (pin "1") (pinfunction "1_1") (pintype "passive"))
      (node (ref "U5") (pin "D-1") (pinfunction "D-_D-1") (pintype "bidirectional"))
    )
    (net (code "75") (name "PIN_BTN") (class "Default")
      (node (ref "K1") (pin "43") (pinfunction "PTC0_43") (pintype "bidirectional"))
      (node (ref "R7") (pin "1") (pinfunction "1_1") (pintype "passive"))
      (node (ref "RST1") (pin "3") (pinfunction "3_3") (pintype "passive"))
    )
    (net (code "76") (name "PIO4") (class "Default")
      (node (ref "R23") (pin "2") (pinfunction "2_2") (pintype "passive"))
      (node (ref "U3") (pin "22") (pinfunction "PIO4_22") (pintype "bidirectional"))
    )
    (net (code "77") (name "RECE1") (class "Default")
      (node (ref "C22") (pin "2") (pinfunction "2_2") (pintype "passive"))
      (node (ref "P8") (pin "31") (pinfunction "31_31") (pintype "passive"))
    )
    (net (code "78") (name "RECE2") (class "Default")
      (node (ref "C27") (pin "2") (pinfunction "2_2") (pintype "passive"))
      (node (ref "P8") (pin "29") (pinfunction "29_29") (pintype "passive"))
    )
    (net (code "79") (name "RTS") (class "Default")
      (node (ref "K1") (pin "44") (pinfunction "PTC1_44") (pintype "bidirectional"))
      (node (ref "U3") (pin "15") (pinfunction "UARTRTS_15") (pintype "bidirectional"))
    )
    (net (code "80") (name "RX1") (class "Default")
      (node (ref "K1") (pin "39") (pinfunction "PTB16_39") (pintype "bidirectional"))
      (node (ref "U3") (pin "14") (pinfunction "UARTTX_14") (pintype "bidirectional"))
    )
    (net (code "81") (name "SCL") (class "Default")
      (node (ref "K1") (pin "50") (pinfunction "PTC5_50") (pintype "bidirectional"))
      (node (ref "U$2") (pin "15") (pinfunction "SCLK_15") (pintype "bidirectional"))
    )
    (net (code "82") (name "SDA") (class "Default")
      (node (ref "K1") (pin "51") (pinfunction "PTC6_51") (pintype "bidirectional"))
      (node (ref "U$2") (pin "14") (pinfunction "SDATA_14") (pintype "bidirectional"))
    )
    (net (code "83") (name "TX1") (class "Default")
      (node (ref "K1") (pin "40") (pinfunction "PTB17_40") (pintype "bidirectional"))
      (node (ref "U3") (pin "13") (pinfunction "UARTRX_13") (pintype "bidirectional"))
    )
    (net (code "84") (name "VBAT_RAW") (class "Default")
      (node (ref "C34") (pin "1") (pinfunction "1_1") (pintype "passive"))
      (node (ref "JP1") (pin "2") (pinfunction "2_2") (pintype "passive"))
      (node (ref "T1") (pin "4") (pinfunction "S_4") (pintype "passive"))
      (node (ref "U4") (pin "3") (pinfunction "VBAT_3") (pintype "power_in"))
    )
    (net (code "85") (name "VCC") (class "Default")
      (node (ref "C26") (pin "2") (pinfunction "2_2") (pintype "passive"))
      (node (ref "C29") (pin "1") (pinfunction "1_1") (pintype "passive"))
      (node (ref "C3") (pin "1") (pinfunction "1_1") (pintype "passive"))
      (node (ref "C32") (pin "1") (pinfunction "1_1") (pintype "passive"))
      (node (ref "C6") (pin "1") (pinfunction "1_1") (pintype "passive"))
      (node (ref "C7") (pin "2") (pinfunction "2_2") (pintype "passive"))
      (node (ref "IC7") (pin "5") (pinfunction "+VS_5") (pintype "input"))
      (node (ref "LP1") (pin "OUT") (pinfunction "OUT_OUT") (pintype "bidirectional"))
      (node (ref "LP1") (pin "SNS") (pinfunction "SNS_SNS") (pintype "bidirectional"))
      (node (ref "R15") (pin "1") (pinfunction "1_1") (pintype "passive"))
      (node (ref "R25") (pin "1") (pinfunction "1_1") (pintype "passive"))
      (node (ref "R26") (pin "1") (pinfunction "1_1") (pintype "passive"))
      (node (ref "U$2") (pin "4") (pinfunction "AVDD_4") (pintype "bidirectional"))
      (node (ref "U$2") (pin "5") (pinfunction "DVDD_5") (pintype "bidirectional"))
      (node (ref "U$3") (pin "P$1") (pinfunction "EN_P$1") (pintype "bidirectional"))
      (node (ref "U$3") (pin "P$4") (pinfunction "VCC_P$4") (pintype "bidirectional"))
      (node (ref "U$4") (pin "1") (pinfunction "+VIN_1") (pintype "bidirectional"))
      (node (ref "U$6") (pin "P1") (pinfunction "VDD_P1") (pintype "power_in"))
    )
    (net (code "86") (name "VCCS_OUT") (class "Default")
      (node (ref "IC4") (pin "3") (pinfunction "IN+_3") (pintype "input"))
      (node (ref "NON_STAF") (pin "2") (pinfunction "2_2") (pintype "passive"))
      (node (ref "P8") (pin "17") (pinfunction "17_17") (pintype "passive"))
      (node (ref "U$6") (pin "P6") (pinfunction "A_P6") (pintype "bidirectional"))
    )
    (net (code "87") (name "VIN") (class "Default")
      (node (ref "C21") (pin "1") (pinfunction "1_1") (pintype "passive"))
      (node (ref "C30") (pin "1") (pinfunction "1_1") (pintype "passive"))
      (node (ref "LP1") (pin "IN") (pinfunction "IN_IN") (pintype "bidirectional"))
      (node (ref "LP1") (pin "IN2") (pinfunction "IN_IN2") (pintype "bidirectional"))
      (node (ref "LP38691") (pin "IN") (pinfunction "IN_IN") (pintype "bidirectional"))
      (node (ref "LP38691") (pin "IN2") (pinfunction "IN_IN2") (pintype "bidirectional"))
      (node (ref "S2") (pin "2") (pinfunction "P_2") (pintype "passive"))
    )
    (net (code "88") (name "VPOWER") (class "Default")
      (node (ref "D5") (pin "C") (pinfunction "C_C") (pintype "passive"))
      (node (ref "S2") (pin "1") (pinfunction "O_1") (pintype "passive"))
      (node (ref "T1") (pin "1") (pinfunction "S_1") (pintype "passive"))
    )
    (net (code "89") (name "VUSB") (class "Default")
      (node (ref "C33") (pin "1") (pinfunction "1_1") (pintype "passive"))
      (node (ref "D5") (pin "A") (pinfunction "A_A") (pintype "passive"))
      (node (ref "R19") (pin "2") (pinfunction "2_2") (pintype "passive"))
      (node (ref "R27") (pin "1") (pinfunction "1_1") (pintype "passive"))
      (node (ref "S2") (pin "3") (pinfunction "S_3") (pintype "passive"))
      (node (ref "T1") (pin "2") (pinfunction "G_2") (pintype "passive"))
      (node (ref "T1") (pin "5") (pinfunction "G_5") (pintype "passive"))
      (node (ref "U4") (pin "4") (pinfunction "VIN_4") (pintype "power_in"))
      (node (ref "U5") (pin "VBUS1") (pinfunction "VBUS_VBUS1") (pintype "bidirectional"))
    )
    (net (code "90") (name "unconnected-(K1-ADC0_DM0-Pad10)") (class "Default")
      (node (ref "K1") (pin "10") (pinfunction "ADC0_DM0_10") (pintype "bidirectional"))
    )
    (net (code "91") (name "unconnected-(K1-ADC0_DM3-Pad12)") (class "Default")
      (node (ref "K1") (pin "12") (pinfunction "ADC0_DM3_12") (pintype "bidirectional"))
    )
    (net (code "92") (name "unconnected-(K1-ADC0_DP0-Pad9)") (class "Default")
      (node (ref "K1") (pin "9") (pinfunction "ADC0_DP0_9") (pintype "bidirectional"))
    )
    (net (code "93") (name "unconnected-(K1-DAC0-Pad18)") (class "Default")
      (node (ref "K1") (pin "18") (pinfunction "DAC0_18") (pintype "bidirectional"))
    )
    (net (code "94") (name "unconnected-(K1-EXTAL32-Pad20)") (class "Default")
      (node (ref "K1") (pin "20") (pinfunction "EXTAL32_20") (pintype "bidirectional"))
    )
    (net (code "95") (name "unconnected-(K1-PTC3-Pad46)") (class "Default")
      (node (ref "K1") (pin "46") (pinfunction "PTC3_46") (pintype "bidirectional"))
    )
    (net (code "96") (name "unconnected-(K1-PTC7-Pad52)") (class "Default")
      (node (ref "K1") (pin "52") (pinfunction "PTC7_52") (pintype "bidirectional"))
    )
    (net (code "97") (name "unconnected-(K1-PTC9-Pad54)") (class "Default")
      (node (ref "K1") (pin "54") (pinfunction "PTC9_54") (pintype "bidirectional"))
    )
    (net (code "98") (name "unconnected-(K1-VREGIN-Pad8)") (class "Default")
      (node (ref "K1") (pin "8") (pinfunction "VREGIN_8") (pintype "bidirectional"))
    )
    (net (code "99") (name "unconnected-(K1-XTAL32-Pad19)") (class "Default")
      (node (ref "K1") (pin "19") (pinfunction "XTAL32_19") (pintype "bidirectional"))
    )
    (net (code "100") (name "unconnected-(P8-Pad19)") (class "Default")
      (node (ref "P8") (pin "19") (pinfunction "19_19") (pintype "passive"))
    )
    (net (code "101") (name "unconnected-(P8-Pad21)") (class "Default")
      (node (ref "P8") (pin "21") (pinfunction "21_21") (pintype "passive"))
    )
    (net (code "102") (name "unconnected-(P8-Pad23)") (class "Default")
      (node (ref "P8") (pin "23") (pinfunction "23_23") (pintype "passive"))
    )
    (net (code "103") (name "unconnected-(P8-Pad25)") (class "Default")
      (node (ref "P8") (pin "25") (pinfunction "25_25") (pintype "passive"))
    )
    (net (code "104") (name "unconnected-(PROG-Pad2)") (class "Default")
      (node (ref "PROG") (pin "2") (pinfunction "2_2") (pintype "passive"))
    )
    (net (code "105") (name "unconnected-(PROG-Pad4)") (class "Default")
      (node (ref "PROG") (pin "4") (pinfunction "4_4") (pintype "passive"))
    )
    (net (code "106") (name "unconnected-(RST-Pad2)") (class "Default")
      (node (ref "RST") (pin "2") (pinfunction "2_2") (pintype "passive"))
    )
    (net (code "107") (name "unconnected-(RST-Pad4)") (class "Default")
      (node (ref "RST") (pin "4") (pinfunction "4_4") (pintype "passive"))
    )
    (net (code "108") (name "unconnected-(RST1-Pad2)") (class "Default")
      (node (ref "RST1") (pin "2") (pinfunction "2_2") (pintype "passive"))
    )
    (net (code "109") (name "unconnected-(RST1-Pad4)") (class "Default")
      (node (ref "RST1") (pin "4") (pinfunction "4_4") (pintype "passive"))
    )
    (net (code "110") (name "unconnected-(U$14-PTA0-Pad14)") (class "Default")
      (node (ref "U$14") (pin "14") (pinfunction "PTA0_14") (pintype "bidirectional"))
    )
    (net (code "111") (name "unconnected-(U$14-PTA1-Pad15)") (class "Default")
      (node (ref "U$14") (pin "15") (pinfunction "PTA1_15") (pintype "bidirectional"))
    )
    (net (code "112") (name "unconnected-(U$14-PTA2-Pad16)") (class "Default")
      (node (ref "U$14") (pin "16") (pinfunction "PTA2_16") (pintype "bidirectional"))
    )
    (net (code "113") (name "unconnected-(U$14-PTA3-Pad3)") (class "Default")
      (node (ref "U$14") (pin "3") (pinfunction "PTA3_3") (pintype "bidirectional"))
    )
    (net (code "114") (name "unconnected-(U$14-PTA5-Pad5)") (class "Default")
      (node (ref "U$14") (pin "5") (pinfunction "PTA5_5") (pintype "bidirectional"))
    )
    (net (code "115") (name "unconnected-(U$14-PTB3-Pad11)") (class "Default")
      (node (ref "U$14") (pin "11") (pinfunction "PTB3_11") (pintype "bidirectional"))
    )
    (net (code "116") (name "unconnected-(U$14-PTB4-Pad12)") (class "Default")
      (node (ref "U$14") (pin "12") (pinfunction "PTB4_12") (pintype "bidirectional"))
    )
    (net (code "117") (name "unconnected-(U3-AIO1-Pad35)") (class "Default")
      (node (ref "U3") (pin "35") (pinfunction "AIO1_35") (pintype "bidirectional"))
    )
    (net (code "118") (name "unconnected-(U3-AIO2-Pad30)") (class "Default")
      (node (ref "U3") (pin "30") (pinfunction "AIO2_30") (pintype "bidirectional"))
    )
    (net (code "119") (name "unconnected-(U3-NC-Pad26)") (class "Default")
      (node (ref "U3") (pin "26") (pinfunction "NC_26") (pintype "bidirectional"))
    )
    (net (code "120") (name "unconnected-(U3-PCMCLK-Pad7)") (class "Default")
      (node (ref "U3") (pin "7") (pinfunction "PCMCLK_7") (pintype "bidirectional"))
    )
    (net (code "121") (name "unconnected-(U3-PCMIN-Pad9)") (class "Default")
      (node (ref "U3") (pin "9") (pinfunction "PCMIN_9") (pintype "bidirectional"))
    )
    (net (code "122") (name "unconnected-(U3-PCMOUT-Pad10)") (class "Default")
      (node (ref "U3") (pin "10") (pinfunction "PCMOUT_10") (pintype "bidirectional"))
    )
    (net (code "123") (name "unconnected-(U3-PCMSYNC-Pad8)") (class "Default")
      (node (ref "U3") (pin "8") (pinfunction "PCMSYNC_8") (pintype "bidirectional"))
    )
    (net (code "124") (name "unconnected-(U3-PIO3-Pad20)") (class "Default")
      (node (ref "U3") (pin "20") (pinfunction "PIO3_20") (pintype "bidirectional"))
    )
    (net (code "125") (name "unconnected-(U3-PIO6-Pad3)") (class "Default")
      (node (ref "U3") (pin "3") (pinfunction "PIO6_3") (pintype "bidirectional"))
    )
    (net (code "126") (name "unconnected-(U3-PIO7-Pad4)") (class "Default")
      (node (ref "U3") (pin "4") (pinfunction "PIO7_4") (pintype "bidirectional"))
    )
    (net (code "127") (name "unconnected-(U3-PIO8-Pad34)") (class "Default")
      (node (ref "U3") (pin "34") (pinfunction "PIO8_34") (pintype "bidirectional"))
    )
    (net (code "128") (name "unconnected-(U3-PIO9-Pad33)") (class "Default")
      (node (ref "U3") (pin "33") (pinfunction "PIO9_33") (pintype "bidirectional"))
    )
    (net (code "129") (name "unconnected-(U3-PIO10-Pad32)") (class "Default")
      (node (ref "U3") (pin "32") (pinfunction "PIO10_32") (pintype "bidirectional"))
    )
    (net (code "130") (name "unconnected-(U3-PIO11-Pad31)") (class "Default")
      (node (ref "U3") (pin "31") (pinfunction "PIO11_31") (pintype "bidirectional"))
    )
    (net (code "131") (name "unconnected-(U3-RESET-Pad5)") (class "Default")
      (node (ref "U3") (pin "5") (pinfunction "RESET_5") (pintype "bidirectional"))
    )
    (net (code "132") (name "unconnected-(U3-SPICLK-Pad6)") (class "Default")
      (node (ref "U3") (pin "6") (pinfunction "SPICLK_6") (pintype "bidirectional"))
    )
    (net (code "133") (name "unconnected-(U3-SPICSB-Pad23)") (class "Default")
      (node (ref "U3") (pin "23") (pinfunction "SPICSB_23") (pintype "bidirectional"))
    )
    (net (code "134") (name "unconnected-(U3-SPIMISO-Pad24)") (class "Default")
      (node (ref "U3") (pin "24") (pinfunction "SPIMISO_24") (pintype "bidirectional"))
    )
    (net (code "135") (name "unconnected-(U3-SPIMOSI-Pad2)") (class "Default")
      (node (ref "U3") (pin "2") (pinfunction "SPIMOSI_2") (pintype "bidirectional"))
    )
    (net (code "136") (name "unconnected-(U3-UARTCTS-Pad16)") (class "Default")
      (node (ref "U3") (pin "16") (pinfunction "UARTCTS_16") (pintype "bidirectional"))
    )
    (net (code "137") (name "unconnected-(U3-USBD+-Pad17)") (class "Default")
      (node (ref "U3") (pin "17") (pinfunction "USBD+_17") (pintype "bidirectional"))
    )
    (net (code "138") (name "unconnected-(U3-USBD--Pad18)") (class "Default")
      (node (ref "U3") (pin "18") (pinfunction "USBD-_18") (pintype "bidirectional"))
    )
  )
)
